# power.net
KiCad netlist of a schematic drawn in Altium Designer
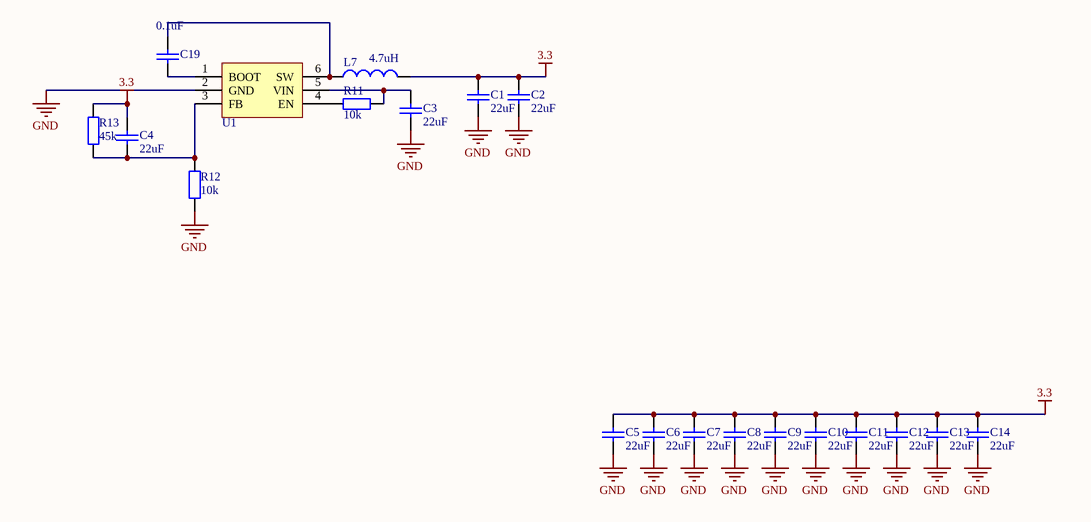
[diagram p0: power.SchDoc]

(export (version "E")
  (design (tool "Eeschema 10.0.6"))
  (components
    (comp (ref "C1")
      (value "22uF")
      (footprint "0805")
      (description "Capacitor")
      (fields (field (name "Comment") "Cap") (field (name "PUBLISHER") "Altium Limited"))
      (libsource (lib "RTC6705") (part "Cap"))
    )
    (comp (ref "C2")
      (value "22uF")
      (footprint "0805")
      (description "Capacitor")
      (fields (field (name "Comment") "Cap") (field (name "PUBLISHER") "Altium Limited"))
      (libsource (lib "RTC6705") (part "Cap"))
    )
    (comp (ref "C3")
      (value "22uF")
      (footprint "0805")
      (description "Capacitor")
      (fields (field (name "Comment") "Cap") (field (name "PUBLISHER") "Altium Limited"))
      (libsource (lib "RTC6705") (part "Cap"))
    )
    (comp (ref "C4")
      (value "22uF")
      (footprint "0402")
      (description "Capacitor")
      (fields (field (name "Comment") "Cap") (field (name "PUBLISHER") "Altium Limited"))
      (libsource (lib "RTC6705") (part "Cap"))
    )
    (comp (ref "C5")
      (value "22uF")
      (footprint "0805")
      (description "Capacitor")
      (fields (field (name "Comment") "Cap") (field (name "PUBLISHER") "Altium Limited"))
      (libsource (lib "RTC6705") (part "Cap"))
    )
    (comp (ref "C6")
      (value "22uF")
      (footprint "0805")
      (description "Capacitor")
      (fields (field (name "Comment") "Cap") (field (name "PUBLISHER") "Altium Limited"))
      (libsource (lib "RTC6705") (part "Cap"))
    )
    (comp (ref "C7")
      (value "22uF")
      (footprint "0805")
      (description "Capacitor")
      (fields (field (name "Comment") "Cap") (field (name "PUBLISHER") "Altium Limited"))
      (libsource (lib "RTC6705") (part "Cap"))
    )
    (comp (ref "C8")
      (value "22uF")
      (footprint "0805")
      (description "Capacitor")
      (fields (field (name "Comment") "Cap") (field (name "PUBLISHER") "Altium Limited"))
      (libsource (lib "RTC6705") (part "Cap"))
    )
    (comp (ref "C9")
      (value "22uF")
      (footprint "0805")
      (description "Capacitor")
      (fields (field (name "Comment") "Cap") (field (name "PUBLISHER") "Altium Limited"))
      (libsource (lib "RTC6705") (part "Cap"))
    )
    (comp (ref "C10")
      (value "22uF")
      (footprint "0805")
      (description "Capacitor")
      (fields (field (name "Comment") "Cap") (field (name "PUBLISHER") "Altium Limited"))
      (libsource (lib "RTC6705") (part "Cap"))
    )
    (comp (ref "C11")
      (value "22uF")
      (footprint "0805")
      (description "Capacitor")
      (fields (field (name "Comment") "Cap") (field (name "PUBLISHER") "Altium Limited"))
      (libsource (lib "RTC6705") (part "Cap"))
    )
    (comp (ref "C12")
      (value "22uF")
      (footprint "0805")
      (description "Capacitor")
      (fields (field (name "Comment") "Cap") (field (name "PUBLISHER") "Altium Limited"))
      (libsource (lib "RTC6705") (part "Cap"))
    )
    (comp (ref "C13")
      (value "22uF")
      (footprint "0805")
      (description "Capacitor")
      (fields (field (name "Comment") "Cap") (field (name "PUBLISHER") "Altium Limited"))
      (libsource (lib "RTC6705") (part "Cap"))
    )
    (comp (ref "C14")
      (value "22uF")
      (footprint "0805")
      (description "Capacitor")
      (fields (field (name "Comment") "Cap") (field (name "PUBLISHER") "Altium Limited"))
      (libsource (lib "RTC6705") (part "Cap"))
    )
    (comp (ref "C19")
      (value "0.1uF")
      (footprint "0402")
      (description "Capacitor")
      (fields (field (name "PUBLISHER") "Altium Limited"))
      (libsource (lib "RTC6705") (part "Cap"))
    )
    (comp (ref "L7")
      (value "4.7uH")
      (footprint "L4015")
      (description "Inductor")
      (fields (field (name "PUBLISHER") "Altium Limited"))
      (libsource (lib "Miscellaneous Devices") (part "Inductor"))
    )
    (comp (ref "R11")
      (value "10k")
      (footprint "0402")
      (description "Resistor")
      (fields (field (name "PUBLISHER") "Altium Limited"))
      (libsource (lib "RTC6705") (part "Res2"))
    )
    (comp (ref "R12")
      (value "10k")
      (footprint "0402")
      (description "Resistor")
      (fields (field (name "PUBLISHER") "Altium Limited"))
      (libsource (lib "") (part "Res2_1"))
    )
    (comp (ref "R13")
      (value "45k")
      (footprint "0402")
      (description "Resistor")
      (fields (field (name "PUBLISHER") "Altium Limited"))
      (libsource (lib "") (part "Res2_1"))
    )
    (comp (ref "U1") (value "RT7295A") (footprint "SOT23-6") (libsource (lib "WifiGain") (part "RT7295A")))
  )
  (nets
    (net (code "1") (name "3.3") (class "Default")
      (node (ref "C1") (pin "2") (pinfunction "2_2") (pintype "passive"))
      (node (ref "C10") (pin "2") (pinfunction "2_2") (pintype "passive"))
      (node (ref "C11") (pin "2") (pinfunction "2_2") (pintype "passive"))
      (node (ref "C12") (pin "2") (pinfunction "2_2") (pintype "passive"))
      (node (ref "C13") (pin "2") (pinfunction "2_2") (pintype "passive"))
      (node (ref "C14") (pin "2") (pinfunction "2_2") (pintype "passive"))
      (node (ref "C2") (pin "2") (pinfunction "2_2") (pintype "passive"))
      (node (ref "C4") (pin "1") (pinfunction "1_1") (pintype "passive"))
      (node (ref "C5") (pin "2") (pinfunction "2_2") (pintype "passive"))
      (node (ref "C6") (pin "2") (pinfunction "2_2") (pintype "passive"))
      (node (ref "C7") (pin "2") (pinfunction "2_2") (pintype "passive"))
      (node (ref "C8") (pin "2") (pinfunction "2_2") (pintype "passive"))
      (node (ref "C9") (pin "2") (pinfunction "2_2") (pintype "passive"))
      (node (ref "L7") (pin "2") (pinfunction "2_2") (pintype "passive"))
      (node (ref "R13") (pin "2") (pinfunction "2_2") (pintype "passive"))
    )
    (net (code "2") (name "GND") (class "Default")
      (node (ref "C1") (pin "1") (pinfunction "1_1") (pintype "passive"))
      (node (ref "C10") (pin "1") (pinfunction "1_1") (pintype "passive"))
      (node (ref "C11") (pin "1") (pinfunction "1_1") (pintype "passive"))
      (node (ref "C12") (pin "1") (pinfunction "1_1") (pintype "passive"))
      (node (ref "C13") (pin "1") (pinfunction "1_1") (pintype "passive"))
      (node (ref "C14") (pin "1") (pinfunction "1_1") (pintype "passive"))
      (node (ref "C2") (pin "1") (pinfunction "1_1") (pintype "passive"))
      (node (ref "C3") (pin "1") (pinfunction "1_1") (pintype "passive"))
      (node (ref "C5") (pin "1") (pinfunction "1_1") (pintype "passive"))
      (node (ref "C6") (pin "1") (pinfunction "1_1") (pintype "passive"))
      (node (ref "C7") (pin "1") (pinfunction "1_1") (pintype "passive"))
      (node (ref "C8") (pin "1") (pinfunction "1_1") (pintype "passive"))
      (node (ref "C9") (pin "1") (pinfunction "1_1") (pintype "passive"))
      (node (ref "R12") (pin "1") (pinfunction "1_1") (pintype "passive"))
      (node (ref "U1") (pin "2") (pinfunction "GND_2") (pintype "passive"))
    )
    (net (code "3") (name "Net-(U1-BOOT)") (class "Default")
      (node (ref "C19") (pin "2") (pinfunction "2_2") (pintype "passive"))
      (node (ref "U1") (pin "1") (pinfunction "BOOT_1") (pintype "passive"))
    )
    (net (code "4") (name "Net-(U1-EN)") (class "Default")
      (node (ref "R11") (pin "1") (pinfunction "1_1") (pintype "passive"))
      (node (ref "U1") (pin "4") (pinfunction "EN_4") (pintype "passive"))
    )
    (net (code "5") (name "Net-(U1-FB)") (class "Default")
      (node (ref "C4") (pin "2") (pinfunction "2_2") (pintype "passive"))
      (node (ref "R12") (pin "2") (pinfunction "2_2") (pintype "passive"))
      (node (ref "R13") (pin "1") (pinfunction "1_1") (pintype "passive"))
      (node (ref "U1") (pin "3") (pinfunction "FB_3") (pintype "passive"))
    )
    (net (code "6") (name "Net-(U1-SW)") (class "Default")
      (node (ref "C19") (pin "1") (pinfunction "1_1") (pintype "passive"))
      (node (ref "L7") (pin "1") (pinfunction "1_1") (pintype "passive"))
      (node (ref "U1") (pin "6") (pinfunction "SW_6") (pintype "passive"))
    )
    (net (code "7") (name "Net-(U1-VIN)") (class "Default")
      (node (ref "C3") (pin "2") (pinfunction "2_2") (pintype "passive"))
      (node (ref "R11") (pin "2") (pinfunction "2_2") (pintype "passive"))
      (node (ref "U1") (pin "5") (pinfunction "VIN_5") (pintype "passive"))
    )
  )
)
